# ARE_adaptadora_dsPIC-PIC32_44pin.net
KiCad netlist of a schematic drawn in EAGLE
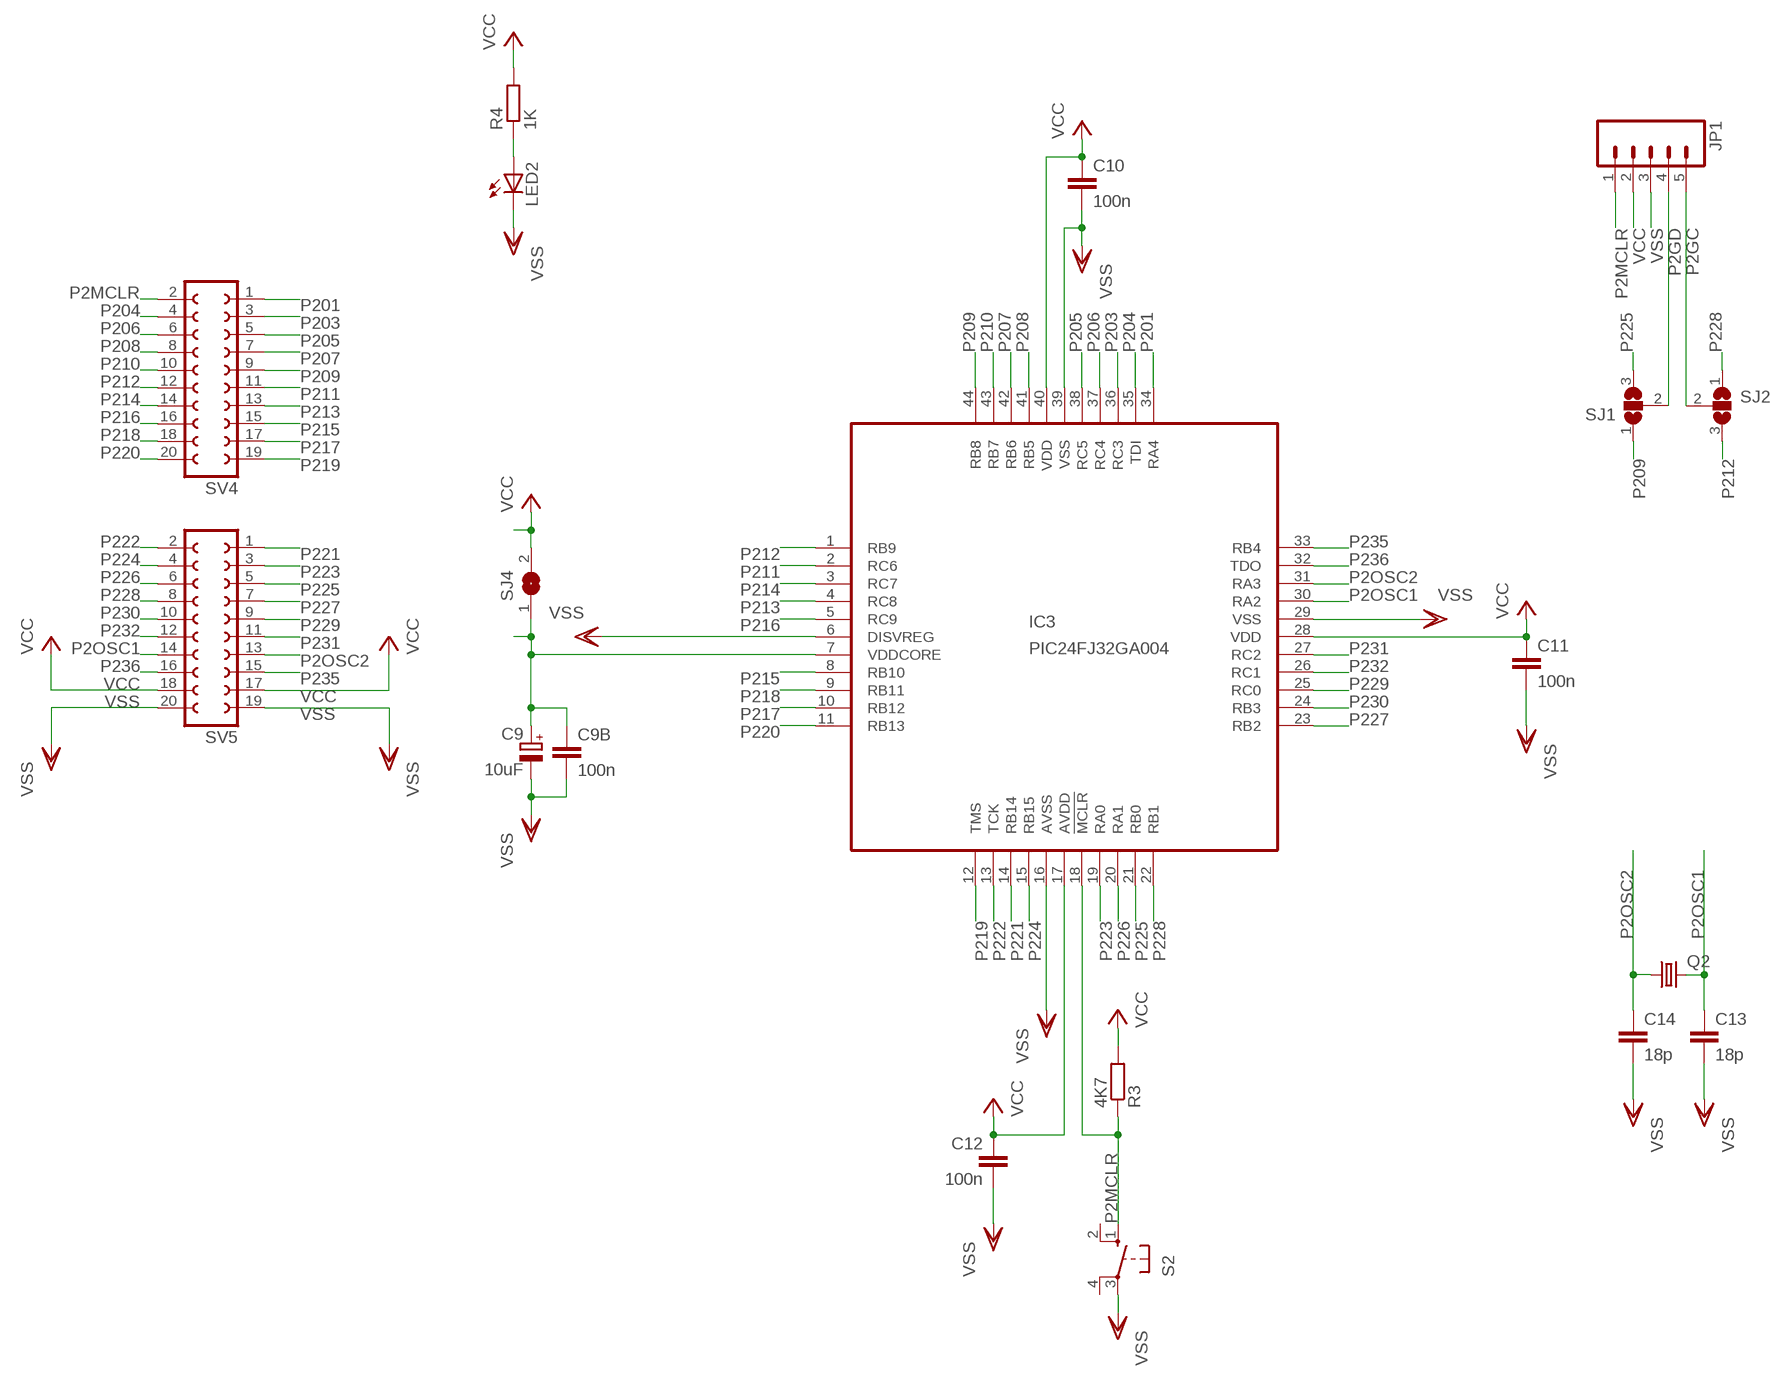
[diagram p0: schematic, sheet 1]

(export (version "E")
  (design (tool "Eeschema 10.0.6"))
  (components
    (comp (ref "C9")
      (value "10uF")
      (footprint "eagle-import:SMC_C")
      (libsource (lib "eagle-import") (part "CPOL-EUSMCC"))
    )
    (comp (ref "C9B")
      (value "100n")
      (footprint "eagle-import:C0805")
      (libsource (lib "eagle-import") (part "C-EUC0805"))
    )
    (comp (ref "C10")
      (value "100n")
      (footprint "eagle-import:C0805")
      (libsource (lib "eagle-import") (part "C-EUC0805"))
    )
    (comp (ref "C11")
      (value "100n")
      (footprint "eagle-import:C0805")
      (libsource (lib "eagle-import") (part "C-EUC0805"))
    )
    (comp (ref "C12")
      (value "100n")
      (footprint "eagle-import:C0805")
      (libsource (lib "eagle-import") (part "C-EUC0805"))
    )
    (comp (ref "C13")
      (value "18p")
      (footprint "eagle-import:C0805")
      (libsource (lib "eagle-import") (part "C-EUC0805"))
    )
    (comp (ref "C14")
      (value "18p")
      (footprint "eagle-import:C0805")
      (libsource (lib "eagle-import") (part "C-EUC0805"))
    )
    (comp (ref "IC3")
      (value "PIC24FJ32GA004")
      (footprint "eagle-import:TQFP44")
      (fields (field (name "MPN") "PIC24FJ32GA004-E/PT"))
      (libsource (lib "eagle-import") (part "PIC24FJ32GA004"))
    )
    (comp (ref "JP1")
      (value "M05PTH")
      (footprint "eagle-import:1X05")
      (libsource (lib "eagle-import") (part "M05PTH"))
    )
    (comp (ref "LED2")
      (value "LEDCHIPLED_0805")
      (footprint "eagle-import:CHIPLED_0805")
      (libsource (lib "eagle-import") (part "LEDCHIPLED_0805"))
    )
    (comp (ref "Q2")
      (value "CRYSTALHC18U-V")
      (footprint "eagle-import:HC18U-V")
      (libsource (lib "eagle-import") (part "CRYSTALHC18U-V"))
    )
    (comp (ref "R3")
      (value "4K7")
      (footprint "eagle-import:R0805")
      (libsource (lib "eagle-import") (part "R-EU_R0805"))
    )
    (comp (ref "R4")
      (value "1K")
      (footprint "eagle-import:R0805")
      (libsource (lib "eagle-import") (part "R-EU_R0805"))
    )
    (comp (ref "S2")
      (value "10-XX")
      (footprint "eagle-import:B3F-10XX")
      (fields
        (field (name "MPN") "B3F-1000")
        (field (name "MPN_1") "B3F-1000")
        (field (name "OC_FARNELL") "176432")
        (field (name "OC_NEWARK") "36M3542")
      )
      (libsource (lib "eagle-import") (part "10-XX"))
    )
    (comp (ref "SJ1")
      (value "SJ2W")
      (footprint "eagle-import:SJ_2")
      (libsource (lib "eagle-import") (part "SJ2W"))
    )
    (comp (ref "SJ2")
      (value "SJ2W")
      (footprint "eagle-import:SJ_2")
      (libsource (lib "eagle-import") (part "SJ2W"))
    )
    (comp (ref "SJ4") (value "SJ") (footprint "eagle-import:SJ") (libsource (lib "eagle-import") (part "SJ")))
    (comp (ref "SV4")
      (value "FE10-2W")
      (footprint "eagle-import:FE10-2W")
      (libsource (lib "eagle-import") (part "FE10-2W"))
    )
    (comp (ref "SV5")
      (value "FE10-2W")
      (footprint "eagle-import:FE10-2W")
      (libsource (lib "eagle-import") (part "FE10-2W"))
    )
  )
  (nets
    (net (code "1") (name "/P2GC") (class "Default")
      (node (ref "JP1") (pin "5") (pinfunction "5_5") (pintype "passive"))
      (node (ref "SJ2") (pin "2") (pinfunction "2_2") (pintype "passive"))
    )
    (net (code "2") (name "/P2GD") (class "Default")
      (node (ref "JP1") (pin "4") (pinfunction "4_4") (pintype "passive"))
      (node (ref "SJ1") (pin "2") (pinfunction "2_2") (pintype "passive"))
    )
    (net (code "3") (name "/P2MCLR") (class "Default")
      (node (ref "IC3") (pin "18") (pinfunction "~{MCLR}_18") (pintype "bidirectional"))
      (node (ref "JP1") (pin "1") (pinfunction "1_1") (pintype "passive"))
      (node (ref "R3") (pin "1") (pinfunction "1_1") (pintype "passive"))
      (node (ref "S2") (pin "1") (pinfunction "S_1") (pintype "passive"))
      (node (ref "SV4") (pin "2") (pinfunction "2_2") (pintype "passive"))
    )
    (net (code "4") (name "/P2OSC1") (class "Default")
      (node (ref "C13") (pin "1") (pinfunction "1_1") (pintype "passive"))
      (node (ref "IC3") (pin "30") (pinfunction "RA2_30") (pintype "bidirectional"))
      (node (ref "Q2") (pin "2") (pinfunction "2_2") (pintype "passive"))
      (node (ref "SV5") (pin "14") (pinfunction "14_14") (pintype "passive"))
    )
    (net (code "5") (name "/P2OSC2") (class "Default")
      (node (ref "C14") (pin "1") (pinfunction "1_1") (pintype "passive"))
      (node (ref "IC3") (pin "31") (pinfunction "RA3_31") (pintype "bidirectional"))
      (node (ref "Q2") (pin "1") (pinfunction "1_1") (pintype "passive"))
      (node (ref "SV5") (pin "13") (pinfunction "13_13") (pintype "passive"))
    )
    (net (code "6") (name "/P201") (class "Default")
      (node (ref "IC3") (pin "34") (pinfunction "RA4_34") (pintype "bidirectional"))
      (node (ref "SV4") (pin "1") (pinfunction "1_1") (pintype "passive"))
    )
    (net (code "7") (name "/P203") (class "Default")
      (node (ref "IC3") (pin "36") (pinfunction "RC3_36") (pintype "bidirectional"))
      (node (ref "SV4") (pin "3") (pinfunction "3_3") (pintype "passive"))
    )
    (net (code "8") (name "/P204") (class "Default")
      (node (ref "IC3") (pin "35") (pinfunction "TDI_35") (pintype "input"))
      (node (ref "SV4") (pin "4") (pinfunction "4_4") (pintype "passive"))
    )
    (net (code "9") (name "/P205") (class "Default")
      (node (ref "IC3") (pin "38") (pinfunction "RC5_38") (pintype "bidirectional"))
      (node (ref "SV4") (pin "5") (pinfunction "5_5") (pintype "passive"))
    )
    (net (code "10") (name "/P206") (class "Default")
      (node (ref "IC3") (pin "37") (pinfunction "RC4_37") (pintype "bidirectional"))
      (node (ref "SV4") (pin "6") (pinfunction "6_6") (pintype "passive"))
    )
    (net (code "11") (name "/P207") (class "Default")
      (node (ref "IC3") (pin "42") (pinfunction "RB6_42") (pintype "bidirectional"))
      (node (ref "SV4") (pin "7") (pinfunction "7_7") (pintype "passive"))
    )
    (net (code "12") (name "/P208") (class "Default")
      (node (ref "IC3") (pin "41") (pinfunction "RB5_41") (pintype "bidirectional"))
      (node (ref "SV4") (pin "8") (pinfunction "8_8") (pintype "passive"))
    )
    (net (code "13") (name "/P209") (class "Default")
      (node (ref "IC3") (pin "44") (pinfunction "RB8_44") (pintype "bidirectional"))
      (node (ref "SJ1") (pin "1") (pinfunction "1_1") (pintype "passive"))
      (node (ref "SV4") (pin "9") (pinfunction "9_9") (pintype "passive"))
    )
    (net (code "14") (name "/P210") (class "Default")
      (node (ref "IC3") (pin "43") (pinfunction "RB7_43") (pintype "bidirectional"))
      (node (ref "SV4") (pin "10") (pinfunction "10_10") (pintype "passive"))
    )
    (net (code "15") (name "/P211") (class "Default")
      (node (ref "IC3") (pin "2") (pinfunction "RC6_2") (pintype "bidirectional"))
      (node (ref "SV4") (pin "11") (pinfunction "11_11") (pintype "passive"))
    )
    (net (code "16") (name "/P212") (class "Default")
      (node (ref "IC3") (pin "1") (pinfunction "RB9_1") (pintype "bidirectional"))
      (node (ref "SJ2") (pin "3") (pinfunction "3_3") (pintype "passive"))
      (node (ref "SV4") (pin "12") (pinfunction "12_12") (pintype "passive"))
    )
    (net (code "17") (name "/P213") (class "Default")
      (node (ref "IC3") (pin "4") (pinfunction "RC8_4") (pintype "bidirectional"))
      (node (ref "SV4") (pin "13") (pinfunction "13_13") (pintype "passive"))
    )
    (net (code "18") (name "/P214") (class "Default")
      (node (ref "IC3") (pin "3") (pinfunction "RC7_3") (pintype "bidirectional"))
      (node (ref "SV4") (pin "14") (pinfunction "14_14") (pintype "passive"))
    )
    (net (code "19") (name "/P215") (class "Default")
      (node (ref "IC3") (pin "8") (pinfunction "RB10_8") (pintype "bidirectional"))
      (node (ref "SV4") (pin "15") (pinfunction "15_15") (pintype "passive"))
    )
    (net (code "20") (name "/P216") (class "Default")
      (node (ref "IC3") (pin "5") (pinfunction "RC9_5") (pintype "bidirectional"))
      (node (ref "SV4") (pin "16") (pinfunction "16_16") (pintype "passive"))
    )
    (net (code "21") (name "/P217") (class "Default")
      (node (ref "IC3") (pin "10") (pinfunction "RB12_10") (pintype "bidirectional"))
      (node (ref "SV4") (pin "17") (pinfunction "17_17") (pintype "passive"))
    )
    (net (code "22") (name "/P218") (class "Default")
      (node (ref "IC3") (pin "9") (pinfunction "RB11_9") (pintype "bidirectional"))
      (node (ref "SV4") (pin "18") (pinfunction "18_18") (pintype "passive"))
    )
    (net (code "23") (name "/P219") (class "Default")
      (node (ref "IC3") (pin "12") (pinfunction "TMS_12") (pintype "input"))
      (node (ref "SV4") (pin "19") (pinfunction "19_19") (pintype "passive"))
    )
    (net (code "24") (name "/P220") (class "Default")
      (node (ref "IC3") (pin "11") (pinfunction "RB13_11") (pintype "bidirectional"))
      (node (ref "SV4") (pin "20") (pinfunction "20_20") (pintype "passive"))
    )
    (net (code "25") (name "/P221") (class "Default")
      (node (ref "IC3") (pin "14") (pinfunction "RB14_14") (pintype "bidirectional"))
      (node (ref "SV5") (pin "1") (pinfunction "1_1") (pintype "passive"))
    )
    (net (code "26") (name "/P222") (class "Default")
      (node (ref "IC3") (pin "13") (pinfunction "TCK_13") (pintype "input"))
      (node (ref "SV5") (pin "2") (pinfunction "2_2") (pintype "passive"))
    )
    (net (code "27") (name "/P223") (class "Default")
      (node (ref "IC3") (pin "19") (pinfunction "RA0_19") (pintype "bidirectional"))
      (node (ref "SV5") (pin "3") (pinfunction "3_3") (pintype "passive"))
    )
    (net (code "28") (name "/P224") (class "Default")
      (node (ref "IC3") (pin "15") (pinfunction "RB15_15") (pintype "bidirectional"))
      (node (ref "SV5") (pin "4") (pinfunction "4_4") (pintype "passive"))
    )
    (net (code "29") (name "/P225") (class "Default")
      (node (ref "IC3") (pin "21") (pinfunction "RB0_21") (pintype "bidirectional"))
      (node (ref "SJ1") (pin "3") (pinfunction "3_3") (pintype "passive"))
      (node (ref "SV5") (pin "5") (pinfunction "5_5") (pintype "passive"))
    )
    (net (code "30") (name "/P226") (class "Default")
      (node (ref "IC3") (pin "20") (pinfunction "RA1_20") (pintype "bidirectional"))
      (node (ref "SV5") (pin "6") (pinfunction "6_6") (pintype "passive"))
    )
    (net (code "31") (name "/P227") (class "Default")
      (node (ref "IC3") (pin "23") (pinfunction "RB2_23") (pintype "bidirectional"))
      (node (ref "SV5") (pin "7") (pinfunction "7_7") (pintype "passive"))
    )
    (net (code "32") (name "/P228") (class "Default")
      (node (ref "IC3") (pin "22") (pinfunction "RB1_22") (pintype "bidirectional"))
      (node (ref "SJ2") (pin "1") (pinfunction "1_1") (pintype "passive"))
      (node (ref "SV5") (pin "8") (pinfunction "8_8") (pintype "passive"))
    )
    (net (code "33") (name "/P229") (class "Default")
      (node (ref "IC3") (pin "25") (pinfunction "RC0_25") (pintype "bidirectional"))
      (node (ref "SV5") (pin "9") (pinfunction "9_9") (pintype "passive"))
    )
    (net (code "34") (name "/P230") (class "Default")
      (node (ref "IC3") (pin "24") (pinfunction "RB3_24") (pintype "bidirectional"))
      (node (ref "SV5") (pin "10") (pinfunction "10_10") (pintype "passive"))
    )
    (net (code "35") (name "/P231") (class "Default")
      (node (ref "IC3") (pin "27") (pinfunction "RC2_27") (pintype "bidirectional"))
      (node (ref "SV5") (pin "11") (pinfunction "11_11") (pintype "passive"))
    )
    (net (code "36") (name "/P232") (class "Default")
      (node (ref "IC3") (pin "26") (pinfunction "RC1_26") (pintype "bidirectional"))
      (node (ref "SV5") (pin "12") (pinfunction "12_12") (pintype "passive"))
    )
    (net (code "37") (name "/P235") (class "Default")
      (node (ref "IC3") (pin "33") (pinfunction "RB4_33") (pintype "bidirectional"))
      (node (ref "SV5") (pin "15") (pinfunction "15_15") (pintype "passive"))
    )
    (net (code "38") (name "/P236") (class "Default")
      (node (ref "IC3") (pin "32") (pinfunction "TDO_32") (pintype "output"))
      (node (ref "SV5") (pin "16") (pinfunction "16_16") (pintype "passive"))
    )
    (net (code "39") (name "Net-(IC3-VDDCORE)") (class "Default")
      (node (ref "C9") (pin "+") (pinfunction "+_+") (pintype "passive"))
      (node (ref "C9B") (pin "1") (pinfunction "1_1") (pintype "passive"))
      (node (ref "IC3") (pin "7") (pinfunction "VDDCORE_7") (pintype "power_in"))
      (node (ref "SJ4") (pin "1") (pinfunction "1_1") (pintype "passive"))
    )
    (net (code "40") (name "Net-(LED2-PadA)") (class "Default")
      (node (ref "LED2") (pin "A") (pinfunction "A_A") (pintype "passive"))
      (node (ref "R4") (pin "1") (pinfunction "1_1") (pintype "passive"))
    )
    (net (code "41") (name "VCC") (class "Default")
      (node (ref "C10") (pin "1") (pinfunction "1_1") (pintype "passive"))
      (node (ref "C11") (pin "1") (pinfunction "1_1") (pintype "passive"))
      (node (ref "C12") (pin "1") (pinfunction "1_1") (pintype "passive"))
      (node (ref "IC3") (pin "17") (pinfunction "AVDD_17") (pintype "power_in"))
      (node (ref "IC3") (pin "28") (pinfunction "VDD_28") (pintype "power_in"))
      (node (ref "IC3") (pin "40") (pinfunction "VDD_40") (pintype "power_in"))
      (node (ref "JP1") (pin "2") (pinfunction "2_2") (pintype "passive"))
      (node (ref "R3") (pin "2") (pinfunction "2_2") (pintype "passive"))
      (node (ref "R4") (pin "2") (pinfunction "2_2") (pintype "passive"))
      (node (ref "SJ4") (pin "2") (pinfunction "2_2") (pintype "passive"))
      (node (ref "SV5") (pin "17") (pinfunction "17_17") (pintype "passive"))
      (node (ref "SV5") (pin "18") (pinfunction "18_18") (pintype "passive"))
    )
    (net (code "42") (name "VSS") (class "Default")
      (node (ref "C10") (pin "2") (pinfunction "2_2") (pintype "passive"))
      (node (ref "C11") (pin "2") (pinfunction "2_2") (pintype "passive"))
      (node (ref "C12") (pin "2") (pinfunction "2_2") (pintype "passive"))
      (node (ref "C13") (pin "2") (pinfunction "2_2") (pintype "passive"))
      (node (ref "C14") (pin "2") (pinfunction "2_2") (pintype "passive"))
      (node (ref "C9") (pin "-") (pinfunction "-_-") (pintype "passive"))
      (node (ref "C9B") (pin "2") (pinfunction "2_2") (pintype "passive"))
      (node (ref "IC3") (pin "16") (pinfunction "AVSS_16") (pintype "power_in"))
      (node (ref "IC3") (pin "29") (pinfunction "VSS_29") (pintype "power_in"))
      (node (ref "IC3") (pin "39") (pinfunction "VSS_39") (pintype "power_in"))
      (node (ref "IC3") (pin "6") (pinfunction "DISVREG_6") (pintype "passive"))
      (node (ref "JP1") (pin "3") (pinfunction "3_3") (pintype "passive"))
      (node (ref "LED2") (pin "C") (pinfunction "C_C") (pintype "passive"))
      (node (ref "S2") (pin "3") (pinfunction "P_3") (pintype "passive"))
      (node (ref "SV5") (pin "19") (pinfunction "19_19") (pintype "passive"))
      (node (ref "SV5") (pin "20") (pinfunction "20_20") (pintype "passive"))
    )
    (net (code "43") (name "unconnected-(S2-P1-Pad4)") (class "Default")
      (node (ref "S2") (pin "4") (pinfunction "P1_4") (pintype "passive"))
    )
    (net (code "44") (name "unconnected-(S2-S1-Pad2)") (class "Default")
      (node (ref "S2") (pin "2") (pinfunction "S1_2") (pintype "passive"))
    )
  )
)
